# 04_Power_Battery.net
KiCad netlist of a schematic drawn in Altium Designer
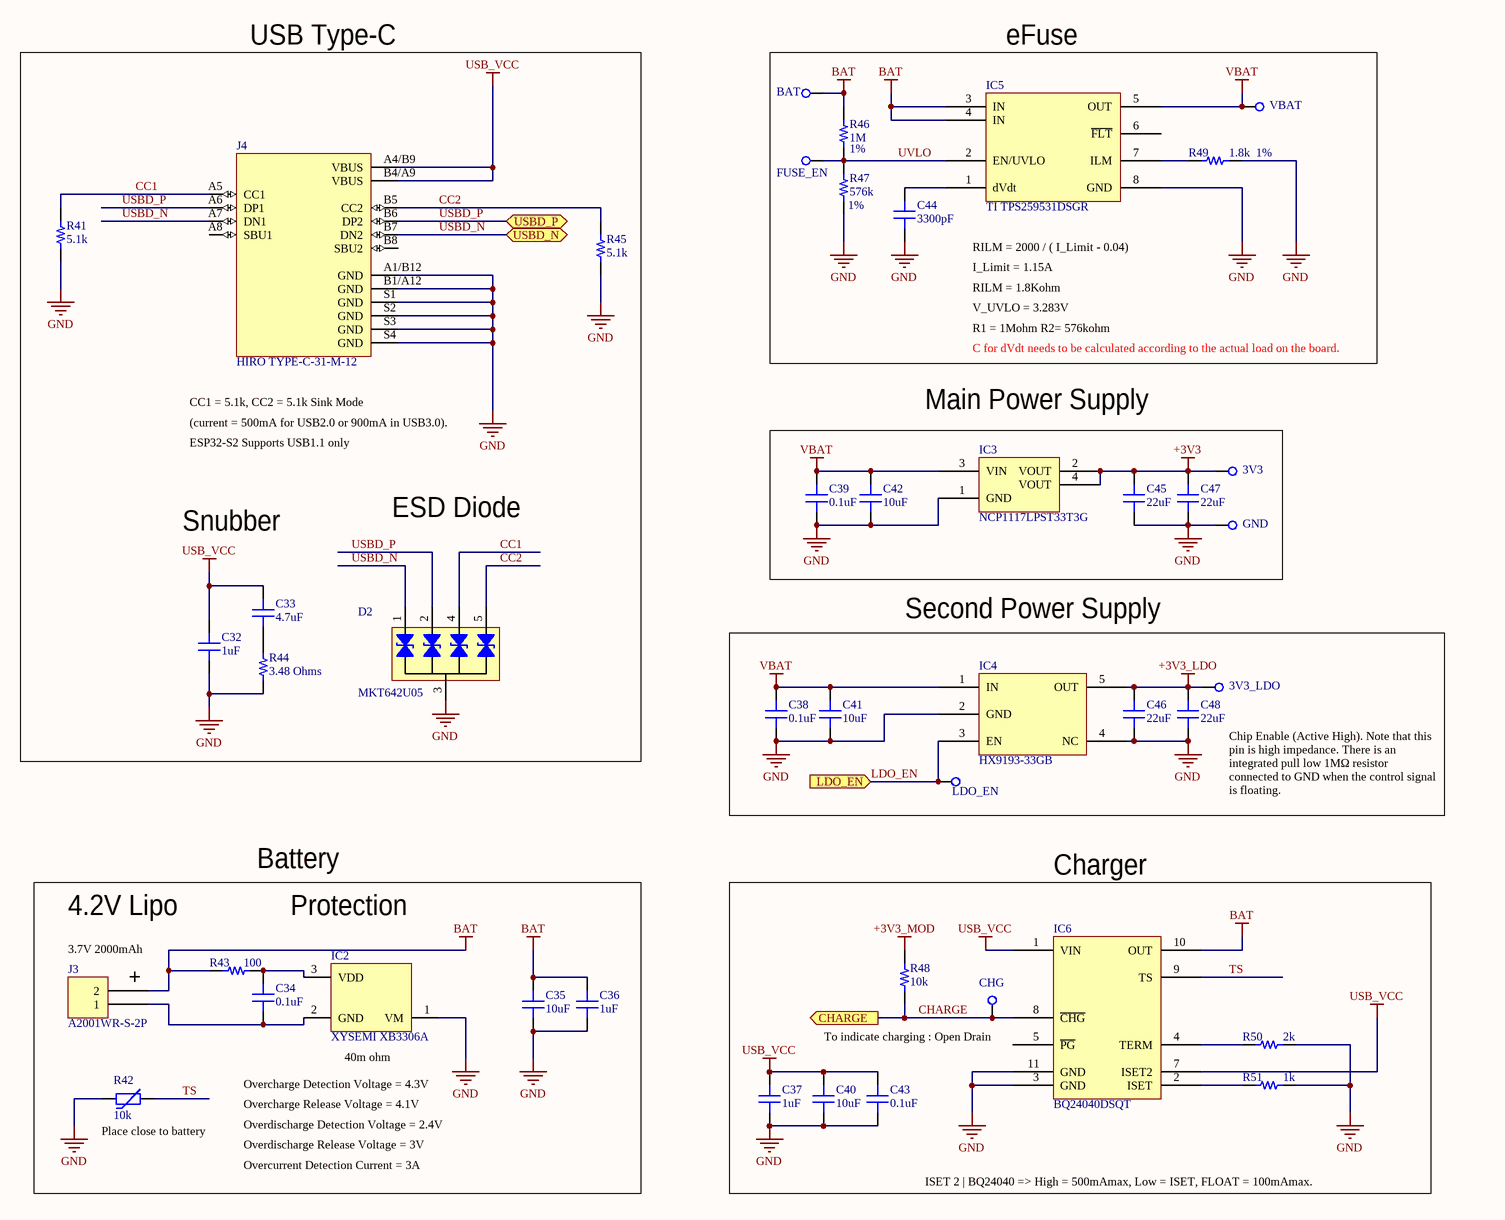
[diagram p0: [04] Power & Battery.SchDoc]

(export (version "E")
  (design (tool "Eeschema 10.0.6"))
  (components
    (comp (ref "3V3")
      (value "RCT-0C")
      (footprint "TE TP 0805")
      (description "0805 PROBE PAD")
      (fields (field (name "MANUFACTURER") "TE Connectivity AMP Connectors"))
      (libsource (lib "Celestial Library Database") (part "Test Point"))
    )
    (comp (ref "3V3_LDO")
      (value "RCT-0C")
      (footprint "TE TP 0805")
      (description "0805 PROBE PAD")
      (fields (field (name "MANUFACTURER") "TE Connectivity AMP Connectors"))
      (libsource (lib "Celestial Library Database") (part "Test Point"))
    )
    (comp (ref "BAT")
      (value "RCT-0C")
      (footprint "3D FootPrint_Backup:0.5mm-TestPad")
      (description "0805 PROBE PAD")
      (fields (field (name "MANUFACTURER") "TE Connectivity AMP Connectors"))
      (libsource (lib "Celestial Library Database") (part "Test Point"))
    )
    (comp (ref "C32")
      (value "1uF")
      (footprint "CAP 0603/1608")
      (description "CAP CER 1UF 10V X7R 0603")
      (fields
        (field (name "PART NUMBER") "CGB3B1X7R1A105K055AC")
        (field (name "MANUFACTURER") "TDK Corporation")
      )
      (libsource (lib "Celestial Library Database") (part "Capacitor"))
    )
    (comp (ref "C33")
      (value "4.7uF")
      (footprint "CAP 0603/1608")
      (description "CAP CER 4.7UF 10V X5R 0603")
      (fields
        (field (name "PART NUMBER") "C1608X5R1A475K080AC")
        (field (name "MANUFACTURER") "TDK Corporation")
      )
      (libsource (lib "Celestial Library Database") (part "Capacitor"))
    )
    (comp (ref "C34")
      (value "0.1uF")
      (footprint "CAP 0603/1608")
      (description "CAP CER 0.1UF 16V X7R 0603")
      (fields (field (name "PART NUMBER") "CC0603KPX7R7BB104") (field (name "MANUFACTURER") "Yageo"))
      (libsource (lib "Celestial Library Database") (part "Capacitor"))
    )
    (comp (ref "C35")
      (value "10uF")
      (footprint "CAP 0603/1608")
      (description "CAP CER 10UF 10V X5R 0603")
      (fields
        (field (name "PART NUMBER") "C1608X5R1A106M080AC")
        (field (name "MANUFACTURER") "TDK Corporation")
      )
      (libsource (lib "Celestial Library Database") (part "Capacitor"))
    )
    (comp (ref "C36")
      (value "1uF")
      (footprint "CAP 0603/1608")
      (description "CAP CER 1UF 10V X7R 0603")
      (fields
        (field (name "PART NUMBER") "CGB3B1X7R1A105K055AC")
        (field (name "MANUFACTURER") "TDK Corporation")
      )
      (libsource (lib "Celestial Library Database") (part "Capacitor"))
    )
    (comp (ref "C37")
      (value "1uF")
      (footprint "CAP 0603/1608")
      (description "CAP CER 1UF 10V X7R 0603")
      (fields
        (field (name "PART NUMBER") "CGB3B1X7R1A105K055AC")
        (field (name "MANUFACTURER") "TDK Corporation")
      )
      (libsource (lib "Celestial Library Database") (part "Capacitor"))
    )
    (comp (ref "C38")
      (value "0.1uF")
      (footprint "CAP 0402/1005")
      (description "CAP CER 0.1UF 10V X7R 0402")
      (fields
        (field (name "PART NUMBER") "C1005X7R1A104K050BB")
        (field (name "MANUFACTURER") "TDK Corporation")
      )
      (libsource (lib "Celestial Library Database") (part "Capacitor"))
    )
    (comp (ref "C39")
      (value "0.1uF")
      (footprint "CAP 0402/1005")
      (description "CAP CER 0.1UF 10V X7R 0402")
      (fields
        (field (name "PART NUMBER") "C1005X7R1A104K050BB")
        (field (name "MANUFACTURER") "TDK Corporation")
      )
      (libsource (lib "Celestial Library Database") (part "Capacitor"))
    )
    (comp (ref "C40")
      (value "10uF")
      (footprint "CAP 0603/1608")
      (description "CAP CER 10UF 10V X5R 0603")
      (fields
        (field (name "PART NUMBER") "C1608X5R1A106M080AC")
        (field (name "MANUFACTURER") "TDK Corporation")
      )
      (libsource (lib "Celestial Library Database") (part "Capacitor"))
    )
    (comp (ref "C41")
      (value "10uF")
      (footprint "CAP 0603/1608")
      (description "CAP CER 10UF 10V X5R 0603")
      (fields
        (field (name "PART NUMBER") "C1608X5R1A106M080AC")
        (field (name "MANUFACTURER") "TDK Corporation")
      )
      (libsource (lib "Celestial Library Database") (part "Capacitor"))
    )
    (comp (ref "C42")
      (value "10uF")
      (footprint "CAP 0603/1608")
      (description "CAP CER 10UF 10V X5R 0603")
      (fields
        (field (name "PART NUMBER") "C1608X5R1A106M080AC")
        (field (name "MANUFACTURER") "TDK Corporation")
      )
      (libsource (lib "Celestial Library Database") (part "Capacitor"))
    )
    (comp (ref "C43")
      (value "0.1uF")
      (footprint "CAP 0402/1005")
      (description "CAP CER 0.1UF 10V X7R 0402")
      (fields
        (field (name "PART NUMBER") "C1005X7R1A104K050BB")
        (field (name "MANUFACTURER") "TDK Corporation")
      )
      (libsource (lib "Celestial Library Database") (part "Capacitor"))
    )
    (comp (ref "C44")
      (value "3300pF")
      (footprint "CAP 0402/1005")
      (description "CAP CER 3300PF 25V X7R 0402")
      (fields
        (field (name "PART NUMBER") "CGJ2B2X7R1E332K050BA")
        (field (name "MANUFACTURER") "TDK Corporation")
      )
      (libsource (lib "Celestial Library Database") (part "Capacitor"))
    )
    (comp (ref "C45")
      (value "22uF")
      (footprint "CAP 0603/1608")
      (description "CAP CER 22UF 10V X5R 0603")
      (fields
        (field (name "PART NUMBER") "C1608X5R1A226M080AC")
        (field (name "MANUFACTURER") "TDK Corporation")
      )
      (libsource (lib "Celestial Library Database") (part "Capacitor"))
    )
    (comp (ref "C46")
      (value "22uF")
      (footprint "CAP 0603/1608")
      (description "CAP CER 22UF 10V X5R 0603")
      (fields
        (field (name "PART NUMBER") "C1608X5R1A226M080AC")
        (field (name "MANUFACTURER") "TDK Corporation")
      )
      (libsource (lib "Celestial Library Database") (part "Capacitor"))
    )
    (comp (ref "C47")
      (value "22uF")
      (footprint "CAP 0603/1608")
      (description "CAP CER 22UF 10V X5R 0603")
      (fields
        (field (name "PART NUMBER") "C1608X5R1A226M080AC")
        (field (name "MANUFACTURER") "TDK Corporation")
      )
      (libsource (lib "Celestial Library Database") (part "Capacitor"))
    )
    (comp (ref "C48")
      (value "22uF")
      (footprint "CAP 0603/1608")
      (description "CAP CER 22UF 10V X5R 0603")
      (fields
        (field (name "PART NUMBER") "C1608X5R1A226M080AC")
        (field (name "MANUFACTURER") "TDK Corporation")
      )
      (libsource (lib "Celestial Library Database") (part "Capacitor"))
    )
    (comp (ref "CHG")
      (value "RCT-0C")
      (footprint "3D FootPrint_Backup:0.5mm-TestPad")
      (description "0805 PROBE PAD")
      (fields (field (name "MANUFACTURER") "TE Connectivity AMP Connectors"))
      (libsource (lib "Celestial Library Database") (part "Test Point"))
    )
    (comp (ref "D2")
      (value "MKT642U05")
      (footprint "TI USON-10 DQA")
      (description "TVS DIODE  4-Channel 5.5VWM 14VC 10SON")
      (fields (field (name "PART NUMBER") "TPD4E05U06DQAR") (field (name "MANUFACTURER") "Texas Instruments"))
      (libsource (lib "Celestial Library Database") (part "TPD4E05U06DQAR"))
    )
    (comp (ref "FUSE_EN")
      (value "RCT-0C")
      (footprint "3D FootPrint_Backup:0.5mm-TestPad")
      (description "0805 PROBE PAD")
      (fields (field (name "MANUFACTURER") "TE Connectivity AMP Connectors"))
      (libsource (lib "Celestial Library Database") (part "Test Point"))
    )
    (comp (ref "GND")
      (value "RCT-0C")
      (footprint "TE TP 0805")
      (description "0805 PROBE PAD")
      (fields (field (name "MANUFACTURER") "TE Connectivity AMP Connectors"))
      (libsource (lib "Celestial Library Database") (part "Test Point"))
    )
    (comp (ref "IC2")
      (value "XYSEMI XB3306A")
      (footprint "DIODES SOT-23-3")
      (description "IC LITHIUM BATT PROTECT SOT23-3")
      (fields (field (name "MANUFACTURER") "XYSEMI"))
      (libsource (lib "Celestial Library Database") (part "XYSEMI XB3306A"))
    )
    (comp (ref "IC3")
      (value "NCP1117LPST33T3G")
      (footprint "ON SEMI SOT-223 ST(318H)")
      (description "IC REG LDO 3.3V 1A SOT223")
      (fields (field (name "MANUFACTURER") "ON Semiconductor"))
      (libsource (lib "Celestial Library Database") (part "ON Semi NCP1117"))
    )
    (comp (ref "IC4")
      (value "HX9193-33GB")
      (footprint "DBV005")
      (description "LDO")
      (libsource (lib "Altium Component") (part "TPS736xx"))
    )
    (comp (ref "IC5")
      (value "TI TPS259531DSGR")
      (footprint "Leadless:TI WSON-8 DSG 2x2MM")
      (libsource (lib "Altium Component") (part "TI TPS259531DSGR"))
    )
    (comp (ref "IC6")
      (value "BQ24040DSQT")
      (footprint "TI PWSON-10 DSQ")
      (description "IC LI-ION CHRG 800MA 6.6V 10SON")
      (fields (field (name "MANUFACTURER") "Texas Instruments"))
      (libsource (lib "Celestial Library Database") (part "TI BQ24040/45"))
    )
    (comp (ref "J3")
      (value "A2001WR-S-2P")
      (footprint "JST S2B-PH-SM4-TB")
      (description "CONN HEADER SMD R/A 2POS 2MM")
      (fields
        (field (name "PART NUMBER") "S2B-PH-SM4-TB(LF)(SN)")
        (field (name "MANUFACTURER") "JST Sales America Inc.")
      )
      (libsource (lib "Celestial Altium Library - altium_library") (part "2 Pin"))
    )
    (comp (ref "J4")
      (value "HIRO TYPE-C-31-M-12")
      (footprint "HIRO TYPE-C-31-M-12")
      (description "CONN USB 2.0 TYPE-C R/A SMT")
      (fields (field (name "MANUFACTURER") "Hiro"))
      (libsource (lib "Celestial Library Database") (part "USB4110-GF-A"))
    )
    (comp (ref "LDO_EN")
      (value "RCT-0C")
      (footprint "3D FootPrint_Backup:0.5mm-TestPad")
      (description "0805 PROBE PAD")
      (fields (field (name "MANUFACTURER") "TE Connectivity AMP Connectors"))
      (libsource (lib "Celestial Library Database") (part "Test Point"))
    )
    (comp (ref "R41")
      (value "5.1k")
      (footprint "RES 0402/1005")
      (description "RES SMD 5.1K OHM 1% 1/10W 0402")
      (fields
        (field (name "PART NUMBER") "ERJ-2RKF5101X")
        (field (name "MANUFACTURER") "Panasonic Electronic Components")
      )
      (libsource (lib "Celestial Library Database") (part "Resistor"))
    )
    (comp (ref "R42")
      (value "~")
      (footprint "FER 0603/1608")
      (description "NTC 0603 10K OHM 5%")
      (fields
        (field (name "PART NUMBER") "B57330V2103J260")
        (field (name "RESISTANCE IN OHMS @ 25C") "10k")
        (field (name "MANUFACTURER") "EPCOS (TDK)")
      )
      (libsource (lib "Celestial Library Database") (part "Thermistor"))
    )
    (comp (ref "R43")
      (value "100")
      (footprint "RES 0603/1608")
      (description "RES SMD 100 OHM 5% 1/10W 0603")
      (fields
        (field (name "PART NUMBER") "ERJ-3GEYJ101V")
        (field (name "MANUFACTURER") "Panasonic Electronic Components")
      )
      (libsource (lib "Celestial Library Database") (part "Resistor"))
    )
    (comp (ref "R44")
      (value "3.48 Ohms")
      (footprint "RES 0805_2012")
      (description "RES SMD 3.48 OHM 1% 1/8W 0805")
      (fields (field (name "PART NUMBER") "RC0805FR-073R48L") (field (name "MANUFACTURER") "Yageo"))
      (libsource (lib "Celestial Altium Library - altium_library") (part "Resistor"))
    )
    (comp (ref "R45")
      (value "5.1k")
      (footprint "RES 0402/1005")
      (description "RES SMD 5.1K OHM 1% 1/10W 0402")
      (fields
        (field (name "PART NUMBER") "ERJ-2RKF5101X")
        (field (name "MANUFACTURER") "Panasonic Electronic Components")
      )
      (libsource (lib "Celestial Library Database") (part "Resistor"))
    )
    (comp (ref "R46")
      (value "1M")
      (footprint "RES 0402/1005")
      (description "RES SMD 1M OHM 1% 1/10W 0402")
      (fields
        (field (name "PART NUMBER") "ERJ-2RKF1004X")
        (field (name "MANUFACTURER") "Panasonic Electronic Components")
        (field (name "TOLERANCE") "1%")
      )
      (libsource (lib "Celestial Library Database") (part "Resistor"))
    )
    (comp (ref "R47")
      (value "576k")
      (footprint "RES 0402/1005")
      (description "RES SMD 576K OHM 1% 1/10W 0402")
      (fields
        (field (name "PART NUMBER") "ERJ-2RKF5763X")
        (field (name "MANUFACTURER") "Panasonic Electronic Components")
        (field (name "TOLERANCE") "1%")
      )
      (libsource (lib "Celestial Library Database") (part "Resistor"))
    )
    (comp (ref "R48")
      (value "10k")
      (footprint "RES 0402/1005")
      (description "RES SMD 10K OHM 5% 1/16W 0402")
      (fields (field (name "PART NUMBER") "RC0402JR-0710KL") (field (name "MANUFACTURER") "Yageo"))
      (libsource (lib "Celestial Library Database") (part "Resistor"))
    )
    (comp (ref "R49")
      (value "1.8k")
      (footprint "RES 0402/1005")
      (description "RES SMD 1.8K OHM 1% 1/10W 0402")
      (fields
        (field (name "PART NUMBER") "ERJ-2RKF1801X")
        (field (name "MANUFACTURER") "Panasonic Electronic Components")
        (field (name "TOLERANCE") "1%")
      )
      (libsource (lib "Celestial Library Database") (part "Resistor"))
    )
    (comp (ref "R50")
      (value "2k")
      (footprint "RES 0402/1005")
      (description "RES SMD 2K OHM 5% 1/10W 0402")
      (fields
        (field (name "PART NUMBER") "ERJ-2GEJ202X")
        (field (name "MANUFACTURER") "Panasonic Electronic Components")
      )
      (libsource (lib "Celestial Library Database") (part "Resistor"))
    )
    (comp (ref "R51")
      (value "1k")
      (footprint "RES 0402/1005")
      (description "RES SMD 1K OHM 1% 1/10W 0402")
      (fields
        (field (name "PART NUMBER") "ERJ-2RKF1001X")
        (field (name "MANUFACTURER") "Panasonic Electronic Components")
      )
      (libsource (lib "Celestial Library Database") (part "Resistor"))
    )
    (comp (ref "VBAT")
      (value "RCT-0C")
      (footprint "3D FootPrint_Backup:0.5mm-TestPad")
      (description "0805 PROBE PAD")
      (fields (field (name "MANUFACTURER") "TE Connectivity AMP Connectors"))
      (libsource (lib "Celestial Library Database") (part "Test Point"))
    )
  )
  (nets
    (net (code "1") (name "+3V3") (class "Default")
      (node (ref "3V3") (pin "1") (pinfunction "TP_1") (pintype "passive"))
      (node (ref "C45") (pin "2") (pinfunction "2_2") (pintype "passive"))
      (node (ref "C47") (pin "2") (pinfunction "2_2") (pintype "passive"))
      (node (ref "IC3") (pin "2") (pinfunction "VOUT_2") (pintype "passive"))
      (node (ref "IC3") (pin "4") (pinfunction "VOUT_4") (pintype "passive"))
    )
    (net (code "2") (name "+3V3_LDO") (class "Default")
      (node (ref "3V3_LDO") (pin "1") (pinfunction "TP_1") (pintype "passive"))
      (node (ref "C46") (pin "2") (pinfunction "2_2") (pintype "passive"))
      (node (ref "C48") (pin "2") (pinfunction "2_2") (pintype "passive"))
      (node (ref "IC4") (pin "5") (pinfunction "OUT_5") (pintype "passive"))
    )
    (net (code "3") (name "+3V3_MOD") (class "Default")
      (node (ref "R48") (pin "2") (pinfunction "2_2") (pintype "passive"))
    )
    (net (code "4") (name "/CC1") (class "Default")
      (node (ref "D2") (pin "4") (pinfunction "D3_4") (pintype "passive"))
      (node (ref "J4") (pin "A5") (pinfunction "CC1_A5") (pintype "bidirectional"))
      (node (ref "R41") (pin "2") (pinfunction "2_2") (pintype "passive"))
    )
    (net (code "5") (name "/CC2") (class "Default")
      (node (ref "D2") (pin "5") (pinfunction "D4_5") (pintype "passive"))
      (node (ref "J4") (pin "B5") (pinfunction "CC2_B5") (pintype "bidirectional"))
      (node (ref "R45") (pin "2") (pinfunction "2_2") (pintype "passive"))
    )
    (net (code "6") (name "/CHARGE") (class "Default")
      (node (ref "CHG") (pin "1") (pinfunction "TP_1") (pintype "passive"))
      (node (ref "IC6") (pin "8") (pinfunction "~{CHG}_8") (pintype "passive"))
      (node (ref "R48") (pin "1") (pinfunction "1_1") (pintype "passive"))
    )
    (net (code "7") (name "/LDO_EN") (class "Default")
      (node (ref "IC4") (pin "3") (pinfunction "EN_3") (pintype "passive"))
      (node (ref "LDO_EN") (pin "1") (pinfunction "TP_1") (pintype "passive"))
    )
    (net (code "8") (name "/TS") (class "Default")
      (node (ref "IC6") (pin "9") (pinfunction "TS_9") (pintype "passive"))
      (node (ref "R42") (pin "2") (pinfunction "2_2") (pintype "passive"))
    )
    (net (code "9") (name "/USBD_N") (class "Default")
      (node (ref "D2") (pin "1") (pinfunction "D1_1") (pintype "passive"))
      (node (ref "J4") (pin "A7") (pinfunction "DN1_A7") (pintype "bidirectional"))
      (node (ref "J4") (pin "B7") (pinfunction "DN2_B7") (pintype "bidirectional"))
    )
    (net (code "10") (name "/USBD_P") (class "Default")
      (node (ref "D2") (pin "2") (pinfunction "D2_2") (pintype "passive"))
      (node (ref "J4") (pin "A6") (pinfunction "DP1_A6") (pintype "bidirectional"))
      (node (ref "J4") (pin "B6") (pinfunction "DP2_B6") (pintype "bidirectional"))
    )
    (net (code "11") (name "/UVLO") (class "Default")
      (node (ref "FUSE_EN") (pin "1") (pinfunction "TP_1") (pintype "passive"))
      (node (ref "IC5") (pin "2") (pinfunction "EN/UVLO_2") (pintype "passive"))
      (node (ref "R46") (pin "1") (pinfunction "1_1") (pintype "passive"))
      (node (ref "R47") (pin "2") (pinfunction "2_2") (pintype "passive"))
    )
    (net (code "12") (name "BAT") (class "Default")
      (node (ref "BAT") (pin "1") (pinfunction "TP_1") (pintype "passive"))
      (node (ref "C35") (pin "2") (pinfunction "2_2") (pintype "passive"))
      (node (ref "C36") (pin "1") (pinfunction "1_1") (pintype "passive"))
      (node (ref "IC5") (pin "3") (pinfunction "IN_3") (pintype "passive"))
      (node (ref "IC5") (pin "4") (pinfunction "IN_4") (pintype "passive"))
      (node (ref "IC6") (pin "10") (pinfunction "OUT_10") (pintype "passive"))
      (node (ref "J3") (pin "2") (pinfunction "2_2") (pintype "passive"))
      (node (ref "R43") (pin "1") (pinfunction "1_1") (pintype "passive"))
      (node (ref "R46") (pin "2") (pinfunction "2_2") (pintype "passive"))
    )
    (net (code "13") (name "GND") (class "Default")
      (node (ref "C32") (pin "2") (pinfunction "2_2") (pintype "passive"))
      (node (ref "C35") (pin "1") (pinfunction "1_1") (pintype "passive"))
      (node (ref "C36") (pin "2") (pinfunction "2_2") (pintype "passive"))
      (node (ref "C37") (pin "2") (pinfunction "2_2") (pintype "passive"))
      (node (ref "C38") (pin "1") (pinfunction "1_1") (pintype "passive"))
      (node (ref "C39") (pin "1") (pinfunction "1_1") (pintype "passive"))
      (node (ref "C40") (pin "1") (pinfunction "1_1") (pintype "passive"))
      (node (ref "C41") (pin "1") (pinfunction "1_1") (pintype "passive"))
      (node (ref "C42") (pin "1") (pinfunction "1_1") (pintype "passive"))
      (node (ref "C43") (pin "1") (pinfunction "1_1") (pintype "passive"))
      (node (ref "C44") (pin "1") (pinfunction "1_1") (pintype "passive"))
      (node (ref "C45") (pin "1") (pinfunction "1_1") (pintype "passive"))
      (node (ref "C46") (pin "1") (pinfunction "1_1") (pintype "passive"))
      (node (ref "C47") (pin "1") (pinfunction "1_1") (pintype "passive"))
      (node (ref "C48") (pin "1") (pinfunction "1_1") (pintype "passive"))
      (node (ref "D2") (pin "3") (pinfunction "GND_3") (pintype "passive"))
      (node (ref "GND") (pin "1") (pinfunction "TP_1") (pintype "passive"))
      (node (ref "IC2") (pin "1") (pinfunction "VM_1") (pintype "passive"))
      (node (ref "IC3") (pin "1") (pinfunction "GND_1") (pintype "passive"))
      (node (ref "IC4") (pin "2") (pinfunction "GND_2") (pintype "passive"))
      (node (ref "IC4") (pin "4") (pinfunction "NC_4") (pintype "passive"))
      (node (ref "IC5") (pin "8") (pinfunction "GND_8") (pintype "passive"))
      (node (ref "IC6") (pin "11") (pinfunction "GND_11") (pintype "passive"))
      (node (ref "IC6") (pin "3") (pinfunction "GND_3") (pintype "passive"))
      (node (ref "J4") (pin "A1/B12") (pinfunction "GND_A1/B12") (pintype "power_in"))
      (node (ref "J4") (pin "B1/A12") (pinfunction "GND_B1/A12") (pintype "power_in"))
      (node (ref "J4") (pin "S1") (pinfunction "GND_S1") (pintype "power_in"))
      (node (ref "J4") (pin "S2") (pinfunction "GND_S2") (pintype "power_in"))
      (node (ref "J4") (pin "S3") (pinfunction "GND_S3") (pintype "power_in"))
      (node (ref "J4") (pin "S4") (pinfunction "GND_S4") (pintype "power_in"))
      (node (ref "R41") (pin "1") (pinfunction "1_1") (pintype "passive"))
      (node (ref "R42") (pin "1") (pinfunction "1_1") (pintype "passive"))
      (node (ref "R44") (pin "1") (pinfunction "1_1") (pintype "passive"))
      (node (ref "R45") (pin "1") (pinfunction "1_1") (pintype "passive"))
      (node (ref "R47") (pin "1") (pinfunction "1_1") (pintype "passive"))
      (node (ref "R49") (pin "2") (pinfunction "2_2") (pintype "passive"))
      (node (ref "R50") (pin "1") (pinfunction "1_1") (pintype "passive"))
      (node (ref "R51") (pin "2") (pinfunction "2_2") (pintype "passive"))
    )
    (net (code "14") (name "Net-(C33-Pad1)") (class "Default")
      (node (ref "C33") (pin "1") (pinfunction "1_1") (pintype "passive"))
      (node (ref "R44") (pin "2") (pinfunction "2_2") (pintype "passive"))
    )
    (net (code "15") (name "Net-(IC2-GND)") (class "Default")
      (node (ref "C34") (pin "2") (pinfunction "2_2") (pintype "passive"))
      (node (ref "IC2") (pin "2") (pinfunction "GND_2") (pintype "passive"))
      (node (ref "J3") (pin "1") (pinfunction "1_1") (pintype "passive"))
    )
    (net (code "16") (name "Net-(IC2-VDD)") (class "Default")
      (node (ref "C34") (pin "1") (pinfunction "1_1") (pintype "passive"))
      (node (ref "IC2") (pin "3") (pinfunction "VDD_3") (pintype "passive"))
      (node (ref "R43") (pin "2") (pinfunction "2_2") (pintype "passive"))
    )
    (net (code "17") (name "Net-(IC5-ILM)") (class "Default")
      (node (ref "IC5") (pin "7") (pinfunction "ILM_7") (pintype "passive"))
      (node (ref "R49") (pin "1") (pinfunction "1_1") (pintype "passive"))
    )
    (net (code "18") (name "Net-(IC5-dVdt)") (class "Default")
      (node (ref "C44") (pin "2") (pinfunction "2_2") (pintype "passive"))
      (node (ref "IC5") (pin "1") (pinfunction "dVdt_1") (pintype "passive"))
    )
    (net (code "19") (name "Net-(IC6-ISET)") (class "Default")
      (node (ref "IC6") (pin "2") (pinfunction "ISET_2") (pintype "passive"))
      (node (ref "R51") (pin "1") (pinfunction "1_1") (pintype "passive"))
    )
    (net (code "20") (name "Net-(IC6-TERM)") (class "Default")
      (node (ref "IC6") (pin "4") (pinfunction "TERM_4") (pintype "passive"))
      (node (ref "R50") (pin "2") (pinfunction "2_2") (pintype "passive"))
    )
    (net (code "21") (name "USB_VCC") (class "Default")
      (node (ref "C32") (pin "1") (pinfunction "1_1") (pintype "passive"))
      (node (ref "C33") (pin "2") (pinfunction "2_2") (pintype "passive"))
      (node (ref "C37") (pin "1") (pinfunction "1_1") (pintype "passive"))
      (node (ref "C40") (pin "2") (pinfunction "2_2") (pintype "passive"))
      (node (ref "C43") (pin "2") (pinfunction "2_2") (pintype "passive"))
      (node (ref "IC6") (pin "1") (pinfunction "VIN_1") (pintype "passive"))
      (node (ref "IC6") (pin "7") (pinfunction "ISET2_7") (pintype "passive"))
      (node (ref "J4") (pin "A4/B9") (pinfunction "VBUS_A4/B9") (pintype "power_in"))
      (node (ref "J4") (pin "B4/A9") (pinfunction "VBUS_B4/A9") (pintype "power_in"))
    )
    (net (code "22") (name "VBAT") (class "Default")
      (node (ref "C38") (pin "2") (pinfunction "2_2") (pintype "passive"))
      (node (ref "C39") (pin "2") (pinfunction "2_2") (pintype "passive"))
      (node (ref "C41") (pin "2") (pinfunction "2_2") (pintype "passive"))
      (node (ref "C42") (pin "2") (pinfunction "2_2") (pintype "passive"))
      (node (ref "IC3") (pin "3") (pinfunction "VIN_3") (pintype "passive"))
      (node (ref "IC4") (pin "1") (pinfunction "IN_1") (pintype "passive"))
      (node (ref "IC5") (pin "5") (pinfunction "OUT_5") (pintype "passive"))
      (node (ref "VBAT") (pin "1") (pinfunction "TP_1") (pintype "passive"))
    )
    (net (code "23") (name "unconnected-(IC5-~{FLT}-Pad6)") (class "Default")
      (node (ref "IC5") (pin "6") (pinfunction "~{FLT}_6") (pintype "passive"))
    )
    (net (code "24") (name "unconnected-(IC6-~{PG}-Pad5)") (class "Default")
      (node (ref "IC6") (pin "5") (pinfunction "~{PG}_5") (pintype "passive"))
    )
    (net (code "25") (name "unconnected-(J4-SBU1-PadA8)") (class "Default")
      (node (ref "J4") (pin "A8") (pinfunction "SBU1_A8") (pintype "bidirectional"))
    )
    (net (code "26") (name "unconnected-(J4-SBU2-PadB8)") (class "Default")
      (node (ref "J4") (pin "B8") (pinfunction "SBU2_B8") (pintype "bidirectional"))
    )
  )
)
